# OLM-base-flora.net
KiCad netlist of a schematic drawn in EAGLE
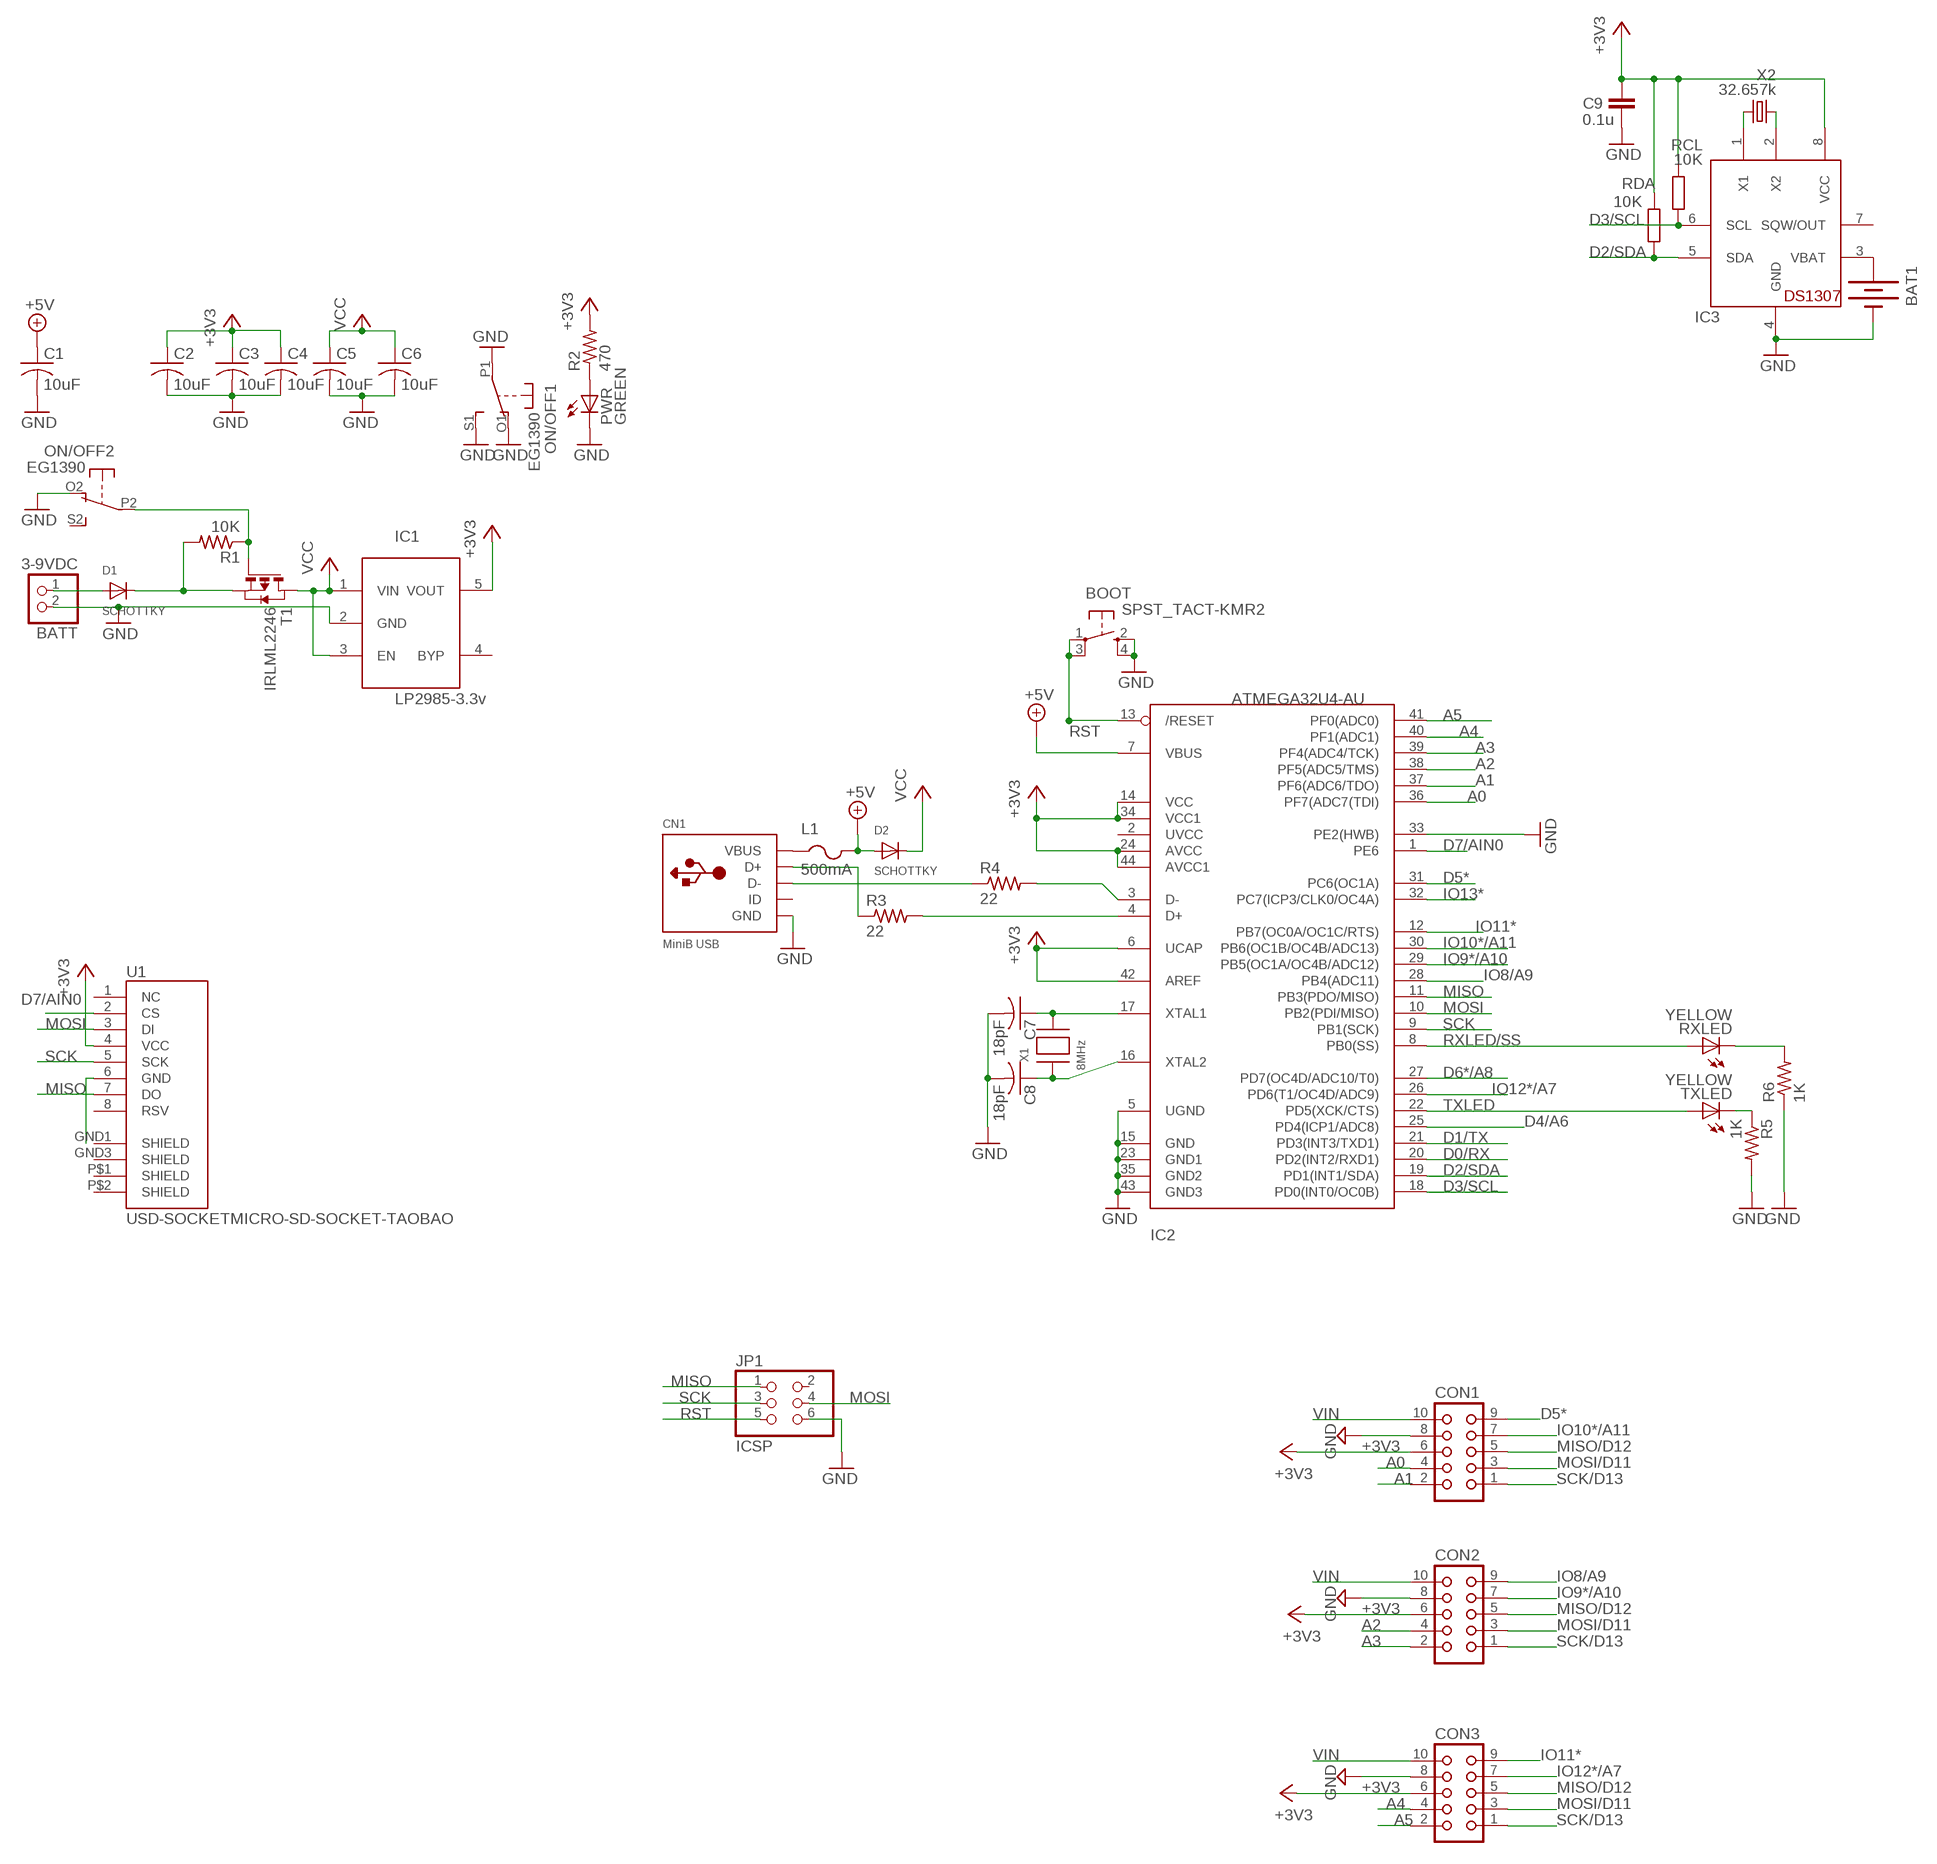
[diagram p0: schematic, sheet 1, part 1 of 2]
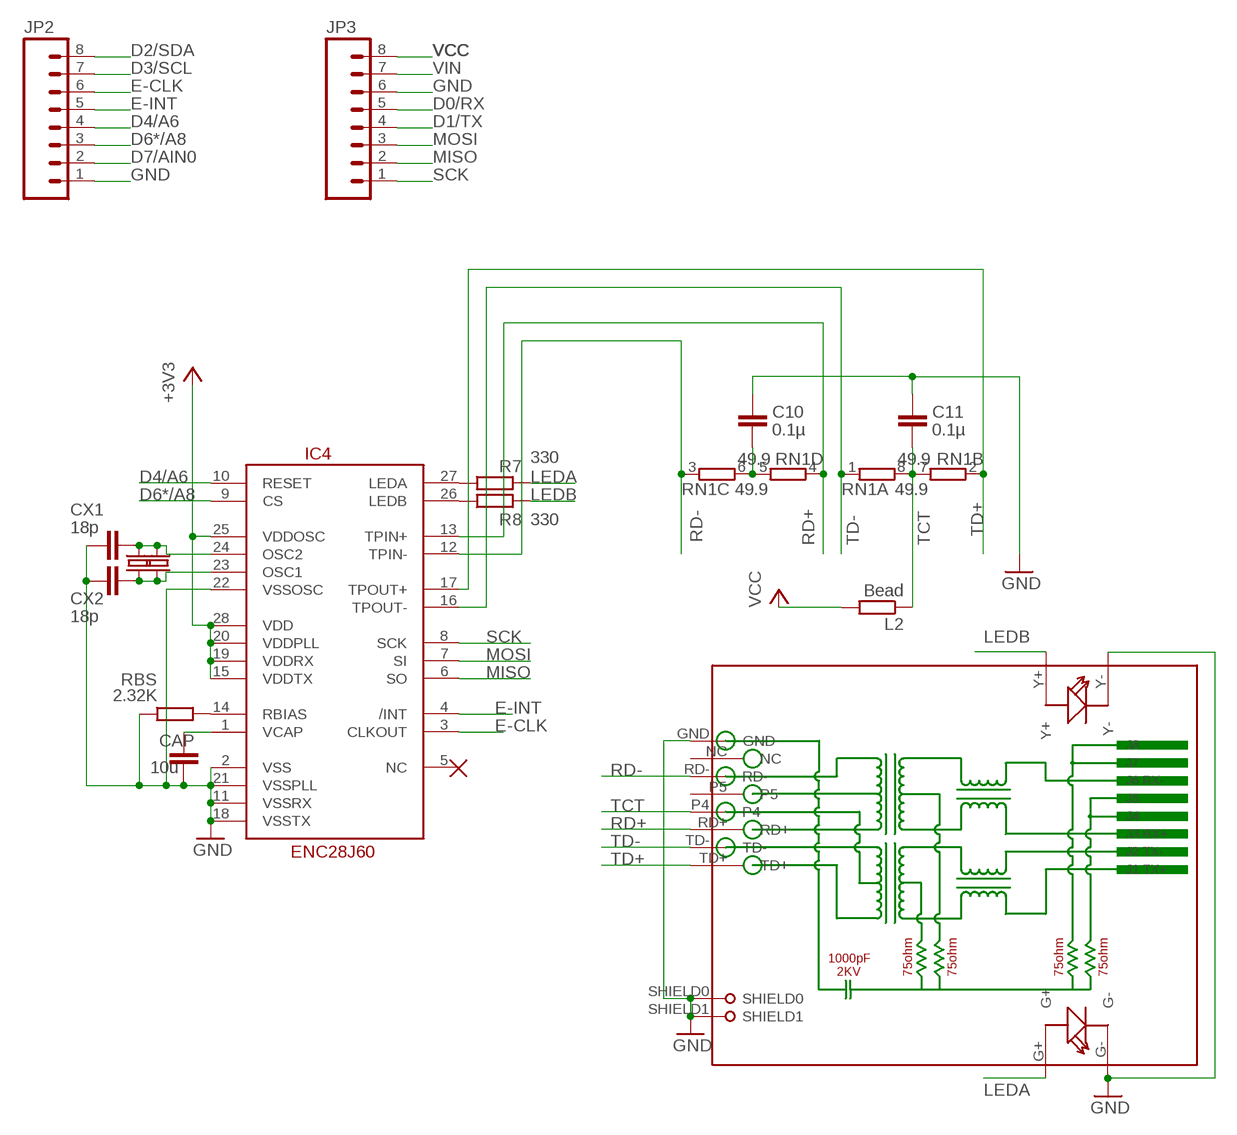
[diagram p1: schematic, sheet 1, part 2 of 2]

(export (version "E")
  (design (tool "Eeschema 10.0.6"))
  (components
    (comp (ref "BAT1")
      (value "BATTERYBATTERY_12MM_SMT")
      (footprint "eagle-import:BATTCON_12MM_SMT")
      (libsource (lib "eagle-import") (part "BATTERYBATTERY_12MM_SMT"))
    )
    (comp (ref "BATT")
      (value "3-9VDC")
      (footprint "eagle-import:JST-PH-2-SMT-RA")
      (libsource (lib "eagle-import") (part "JST_2PIN-SMT-RA"))
    )
    (comp (ref "BOOT")
      (value "SPST_TACT-KMR2")
      (footprint "eagle-import:KMR2")
      (libsource (lib "eagle-import") (part "SPST_TACT-KMR2"))
    )
    (comp (ref "C1")
      (value "10uF")
      (footprint "eagle-import:C0805K")
      (libsource (lib "eagle-import") (part "C-USC0805K"))
    )
    (comp (ref "C2")
      (value "10uF")
      (footprint "eagle-import:C0805K")
      (libsource (lib "eagle-import") (part "C-USC0805K"))
    )
    (comp (ref "C3")
      (value "10uF")
      (footprint "eagle-import:C0805K")
      (libsource (lib "eagle-import") (part "C-USC0805K"))
    )
    (comp (ref "C4")
      (value "10uF")
      (footprint "eagle-import:C0805K")
      (libsource (lib "eagle-import") (part "C-USC0805K"))
    )
    (comp (ref "C5")
      (value "10uF")
      (footprint "eagle-import:C0805K")
      (libsource (lib "eagle-import") (part "C-USC0805K"))
    )
    (comp (ref "C6")
      (value "10uF")
      (footprint "eagle-import:C0805K")
      (libsource (lib "eagle-import") (part "C-USC0805K"))
    )
    (comp (ref "C7")
      (value "18pF")
      (footprint "eagle-import:C0805K")
      (libsource (lib "eagle-import") (part "C-USC0805K"))
    )
    (comp (ref "C8")
      (value "18pF")
      (footprint "eagle-import:C0805K")
      (libsource (lib "eagle-import") (part "C-USC0805K"))
    )
    (comp (ref "C9")
      (value "0.1u")
      (footprint "eagle-import:C0805")
      (libsource (lib "eagle-import") (part "C-EUC0805"))
    )
    (comp (ref "C10")
      (value "0.1µ")
      (footprint "eagle-import:C0805")
      (libsource (lib "eagle-import") (part "resistor_C-EUC0805"))
    )
    (comp (ref "C11")
      (value "0.1µ")
      (footprint "eagle-import:C0805")
      (libsource (lib "eagle-import") (part "resistor_C-EUC0805"))
    )
    (comp (ref "CAP")
      (value "10u")
      (footprint "eagle-import:C0805")
      (libsource (lib "eagle-import") (part "resistor_C-EUC0805"))
    )
    (comp (ref "CN1")
      (value "MiniB USB")
      (footprint "eagle-import:USB-MINIB_LARGER")
      (libsource (lib "eagle-import") (part "USBMINIBLARGE"))
    )
    (comp (ref "CON1")
      (value "CON10L")
      (footprint "eagle-import:CON10L")
      (libsource (lib "eagle-import") (part "CON10L"))
    )
    (comp (ref "CON2")
      (value "CON10L")
      (footprint "eagle-import:CON10L")
      (libsource (lib "eagle-import") (part "CON10L"))
    )
    (comp (ref "CON3")
      (value "CON10L")
      (footprint "eagle-import:CON10L")
      (libsource (lib "eagle-import") (part "CON10L"))
    )
    (comp (ref "CX1")
      (value "18p")
      (footprint "eagle-import:C0805")
      (libsource (lib "eagle-import") (part "resistor_C-EUC0805"))
    )
    (comp (ref "CX2")
      (value "18p")
      (footprint "eagle-import:C0805")
      (libsource (lib "eagle-import") (part "resistor_C-EUC0805"))
    )
    (comp (ref "D1")
      (value "SCHOTTKY")
      (footprint "eagle-import:SOD-123")
      (libsource (lib "eagle-import") (part "DIODESOD-123"))
    )
    (comp (ref "D2")
      (value "SCHOTTKY")
      (footprint "eagle-import:SOD-123")
      (libsource (lib "eagle-import") (part "DIODESOD-123"))
    )
    (comp (ref "IC1")
      (value "LP2985-3.3v")
      (footprint "eagle-import:SOT23-5L")
      (libsource (lib "eagle-import") (part "LP298XS"))
    )
    (comp (ref "IC2")
      (value "ATMEGA32U4-AU")
      (footprint "eagle-import:TQFP44")
      (libsource (lib "eagle-import") (part "ATMEGA32U4-AU"))
    )
    (comp (ref "IC3")
      (value "DS1307")
      (footprint "eagle-import:SO08")
      (libsource (lib "eagle-import") (part "DS1307SOIC"))
    )
    (comp (ref "IC4")
      (value "ENC28J60")
      (footprint "eagle-import:SOIC28WLONG")
      (libsource (lib "eagle-import") (part "ENC28J60SO28LONG"))
    )
    (comp (ref "JP1")
      (value "ICSP")
      (footprint "eagle-import:2X03")
      (libsource (lib "eagle-import") (part "PINHD-2X3"))
    )
    (comp (ref "JP2")
      (value "M08LOCK")
      (footprint "eagle-import:1X08_LOCK")
      (libsource (lib "eagle-import") (part "M08LOCK"))
    )
    (comp (ref "JP3")
      (value "M08LOCK")
      (footprint "eagle-import:1X08_LOCK")
      (libsource (lib "eagle-import") (part "M08LOCK"))
    )
    (comp (ref "L1")
      (value "500mA")
      (footprint "eagle-import:R1206")
      (libsource (lib "eagle-import") (part "PTCFUSE-1206"))
    )
    (comp (ref "L2")
      (value "Bead")
      (footprint "eagle-import:R0805")
      (libsource (lib "eagle-import") (part "R-EU_R0805"))
    )
    (comp (ref "ON/OFF")
      (value "EG1390")
      (footprint "eagle-import:EG1390")
      (libsource (lib "eagle-import") (part "DPDT-EG1390"))
    )
    (comp (ref "PWR")
      (value "GREEN")
      (footprint "eagle-import:CHIPLED_0805")
      (libsource (lib "eagle-import") (part "LEDCHIPLED_0805"))
    )
    (comp (ref "R1")
      (value "10K")
      (footprint "eagle-import:R0805")
      (libsource (lib "eagle-import") (part "R-US_R0805"))
    )
    (comp (ref "R2")
      (value "470")
      (footprint "eagle-import:R0805")
      (libsource (lib "eagle-import") (part "R-US_R0805"))
    )
    (comp (ref "R3")
      (value "22")
      (footprint "eagle-import:R0805")
      (libsource (lib "eagle-import") (part "R-US_R0805"))
    )
    (comp (ref "R4")
      (value "22")
      (footprint "eagle-import:R0805")
      (libsource (lib "eagle-import") (part "R-US_R0805"))
    )
    (comp (ref "R5")
      (value "1K")
      (footprint "eagle-import:R0805")
      (libsource (lib "eagle-import") (part "R-US_R0805"))
    )
    (comp (ref "R6")
      (value "1K")
      (footprint "eagle-import:R0805")
      (libsource (lib "eagle-import") (part "R-US_R0805"))
    )
    (comp (ref "R7")
      (value "330")
      (footprint "eagle-import:R0805")
      (libsource (lib "eagle-import") (part "R-EU_R0805"))
    )
    (comp (ref "R8")
      (value "330")
      (footprint "eagle-import:R0805")
      (libsource (lib "eagle-import") (part "R-EU_R0805"))
    )
    (comp (ref "RBS")
      (value "2.32K")
      (footprint "eagle-import:R0805")
      (libsource (lib "eagle-import") (part "R-EU_R0805"))
    )
    (comp (ref "RCL")
      (value "10K")
      (footprint "eagle-import:R0805")
      (libsource (lib "eagle-import") (part "R-EU_R0805"))
    )
    (comp (ref "RDA")
      (value "10K")
      (footprint "eagle-import:R0805")
      (libsource (lib "eagle-import") (part "R-EU_R0805"))
    )
    (comp (ref "RJ1")
      (value "HR911105A")
      (footprint "eagle-import:HR911105A")
      (libsource (lib "eagle-import") (part "HR911105A"))
    )
    (comp (ref "RN1")
      (value "49.9")
      (footprint "eagle-import:EXB38V")
      (libsource (lib "eagle-import") (part "4R-NEXB38V"))
    )
    (comp (ref "RXLED")
      (value "YELLOW")
      (footprint "eagle-import:CHIPLED_0805")
      (libsource (lib "eagle-import") (part "LEDCHIPLED_0805"))
    )
    (comp (ref "T1")
      (value "IRLML2246")
      (footprint "eagle-import:SOT-23")
      (libsource (lib "eagle-import") (part "PMOSSOT23"))
    )
    (comp (ref "TXLED")
      (value "YELLOW")
      (footprint "eagle-import:CHIPLED_0805")
      (libsource (lib "eagle-import") (part "LEDCHIPLED_0805"))
    )
    (comp (ref "U1")
      (value "USD-SOCKETMICRO-SD-SOCKET-TAOBAO")
      (footprint "eagle-import:MICRO-SD-SOCKET-TAOBAO")
      (libsource (lib "eagle-import") (part "USD-SOCKETMICRO-SD-SOCKET-TAOBAO"))
    )
    (comp (ref "X1")
      (value "8MHz")
      (footprint "eagle-import:NX5032")
      (libsource (lib "eagle-import") (part "XTALNX5032"))
    )
    (comp (ref "X2")
      (value "32.657k")
      (footprint "eagle-import:TC26H")
      (libsource (lib "eagle-import") (part "crystal_CRYSTALTC26H"))
    )
    (comp (ref "X2A")
      (value "25MHz")
      (footprint "eagle-import:CRYSTAL-SMD-10.5X4.8-2PIN")
      (libsource (lib "eagle-import") (part "CRYSTAL10.5X4.8"))
    )
    (comp (ref "X2A1")
      (value "25MHz")
      (footprint "eagle-import:HC49US")
      (libsource (lib "eagle-import") (part "CRYSTALHC49US"))
    )
  )
  (nets
    (net (code "1") (name "+3V3") (class "Default")
      (node (ref "C2") (pin "1") (pinfunction "1_1") (pintype "passive"))
      (node (ref "C3") (pin "1") (pinfunction "1_1") (pintype "passive"))
      (node (ref "C4") (pin "1") (pinfunction "1_1") (pintype "passive"))
      (node (ref "C9") (pin "1") (pinfunction "1_1") (pintype "passive"))
      (node (ref "CON1") (pin "6") (pinfunction "6_6") (pintype "passive"))
      (node (ref "CON2") (pin "6") (pinfunction "6_6") (pintype "passive"))
      (node (ref "CON3") (pin "6") (pinfunction "6_6") (pintype "passive"))
      (node (ref "IC1") (pin "5") (pinfunction "VOUT_5") (pintype "bidirectional"))
      (node (ref "IC2") (pin "14") (pinfunction "VCC_14") (pintype "bidirectional"))
      (node (ref "IC2") (pin "24") (pinfunction "AVCC_24") (pintype "bidirectional"))
      (node (ref "IC2") (pin "34") (pinfunction "VCC1_34") (pintype "bidirectional"))
      (node (ref "IC2") (pin "42") (pinfunction "AREF_42") (pintype "bidirectional"))
      (node (ref "IC2") (pin "44") (pinfunction "AVCC1_44") (pintype "bidirectional"))
      (node (ref "IC2") (pin "6") (pinfunction "UCAP_6") (pintype "bidirectional"))
      (node (ref "IC3") (pin "8") (pinfunction "VCC_8") (pintype "power_in"))
      (node (ref "IC4") (pin "15") (pinfunction "VDDTX_15") (pintype "bidirectional"))
      (node (ref "IC4") (pin "19") (pinfunction "VDDRX_19") (pintype "bidirectional"))
      (node (ref "IC4") (pin "20") (pinfunction "VDDPLL_20") (pintype "bidirectional"))
      (node (ref "IC4") (pin "25") (pinfunction "VDDOSC_25") (pintype "bidirectional"))
      (node (ref "IC4") (pin "28") (pinfunction "VDD_28") (pintype "bidirectional"))
      (node (ref "R2") (pin "2") (pinfunction "2_2") (pintype "passive"))
      (node (ref "RCL") (pin "1") (pinfunction "1_1") (pintype "passive"))
      (node (ref "RDA") (pin "1") (pinfunction "1_1") (pintype "passive"))
      (node (ref "U1") (pin "4") (pinfunction "VCC_4") (pintype "bidirectional"))
    )
    (net (code "2") (name "+5V") (class "Default")
      (node (ref "C1") (pin "1") (pinfunction "1_1") (pintype "passive"))
      (node (ref "D2") (pin "A") (pinfunction "A_A") (pintype "passive"))
      (node (ref "IC2") (pin "7") (pinfunction "VBUS_7") (pintype "bidirectional"))
      (node (ref "L1") (pin "2") (pinfunction "2_2") (pintype "passive"))
    )
    (net (code "3") (name "/A0") (class "Default")
      (node (ref "CON1") (pin "4") (pinfunction "4_4") (pintype "passive"))
      (node (ref "IC2") (pin "36") (pinfunction "PF7(ADC7(TDI)_36") (pintype "bidirectional"))
    )
    (net (code "4") (name "/A1") (class "Default")
      (node (ref "CON1") (pin "2") (pinfunction "2_2") (pintype "passive"))
      (node (ref "IC2") (pin "37") (pinfunction "PF6(ADC6/TDO)_37") (pintype "bidirectional"))
    )
    (net (code "5") (name "/A2") (class "Default")
      (node (ref "CON2") (pin "4") (pinfunction "4_4") (pintype "passive"))
      (node (ref "IC2") (pin "38") (pinfunction "PF5(ADC5/TMS)_38") (pintype "bidirectional"))
    )
    (net (code "6") (name "/A3") (class "Default")
      (node (ref "CON2") (pin "2") (pinfunction "2_2") (pintype "passive"))
      (node (ref "IC2") (pin "39") (pinfunction "PF4(ADC4/TCK)_39") (pintype "bidirectional"))
    )
    (net (code "7") (name "/A4") (class "Default")
      (node (ref "CON3") (pin "4") (pinfunction "4_4") (pintype "passive"))
      (node (ref "IC2") (pin "40") (pinfunction "PF1(ADC1)_40") (pintype "bidirectional"))
    )
    (net (code "8") (name "/A5") (class "Default")
      (node (ref "CON3") (pin "2") (pinfunction "2_2") (pintype "passive"))
      (node (ref "IC2") (pin "41") (pinfunction "PF0(ADC0)_41") (pintype "bidirectional"))
    )
    (net (code "9") (name "/D0{slash}RX") (class "Default")
      (node (ref "IC2") (pin "20") (pinfunction "PD2(INT2/RXD1)_20") (pintype "bidirectional"))
      (node (ref "JP3") (pin "5") (pinfunction "5_5") (pintype "passive"))
    )
    (net (code "10") (name "/D1{slash}TX") (class "Default")
      (node (ref "IC2") (pin "21") (pinfunction "PD3(INT3/TXD1)_21") (pintype "bidirectional"))
      (node (ref "JP3") (pin "4") (pinfunction "4_4") (pintype "passive"))
    )
    (net (code "11") (name "/D2{slash}SDA") (class "Default")
      (node (ref "IC2") (pin "19") (pinfunction "PD1(INT1/SDA)_19") (pintype "bidirectional"))
      (node (ref "IC3") (pin "5") (pinfunction "SDA_5") (pintype "bidirectional"))
      (node (ref "JP2") (pin "8") (pinfunction "8_8") (pintype "passive"))
      (node (ref "RDA") (pin "2") (pinfunction "2_2") (pintype "passive"))
    )
    (net (code "12") (name "/D3{slash}SCL") (class "Default")
      (node (ref "IC2") (pin "18") (pinfunction "PD0(INT0/OC0B)_18") (pintype "bidirectional"))
      (node (ref "IC3") (pin "6") (pinfunction "SCL_6") (pintype "bidirectional"))
      (node (ref "JP2") (pin "7") (pinfunction "7_7") (pintype "passive"))
      (node (ref "RCL") (pin "2") (pinfunction "2_2") (pintype "passive"))
    )
    (net (code "13") (name "/D4{slash}A6") (class "Default")
      (node (ref "IC2") (pin "25") (pinfunction "PD4(ICP1/ADC8)_25") (pintype "bidirectional"))
      (node (ref "IC4") (pin "10") (pinfunction "RESET_10") (pintype "bidirectional"))
      (node (ref "JP2") (pin "4") (pinfunction "4_4") (pintype "passive"))
    )
    (net (code "14") (name "/D5*") (class "Default")
      (node (ref "CON1") (pin "9") (pinfunction "9_9") (pintype "passive"))
      (node (ref "IC2") (pin "31") (pinfunction "PC6(OC1A)_31") (pintype "bidirectional"))
    )
    (net (code "15") (name "/D6*{slash}A8") (class "Default")
      (node (ref "IC2") (pin "27") (pinfunction "PD7(OC4D/ADC10/T0)_27") (pintype "bidirectional"))
      (node (ref "IC4") (pin "9") (pinfunction "CS_9") (pintype "bidirectional"))
      (node (ref "JP2") (pin "3") (pinfunction "3_3") (pintype "passive"))
    )
    (net (code "16") (name "/D7{slash}AIN0") (class "Default")
      (node (ref "IC2") (pin "1") (pinfunction "PE6_1") (pintype "bidirectional"))
      (node (ref "JP2") (pin "2") (pinfunction "2_2") (pintype "passive"))
      (node (ref "U1") (pin "2") (pinfunction "CS_2") (pintype "bidirectional"))
    )
    (net (code "17") (name "/E-CLK") (class "Default")
      (node (ref "IC4") (pin "3") (pinfunction "CLKOUT_3") (pintype "bidirectional"))
      (node (ref "JP2") (pin "6") (pinfunction "6_6") (pintype "passive"))
    )
    (net (code "18") (name "/E-INT") (class "Default")
      (node (ref "IC4") (pin "4") (pinfunction "/INT_4") (pintype "bidirectional"))
      (node (ref "JP2") (pin "5") (pinfunction "5_5") (pintype "passive"))
    )
    (net (code "19") (name "/IO8{slash}A9") (class "Default")
      (node (ref "CON2") (pin "9") (pinfunction "9_9") (pintype "passive"))
      (node (ref "IC2") (pin "28") (pinfunction "PB4(ADC11)_28") (pintype "bidirectional"))
    )
    (net (code "20") (name "/IO9*{slash}A10") (class "Default")
      (node (ref "CON2") (pin "7") (pinfunction "7_7") (pintype "passive"))
      (node (ref "IC2") (pin "29") (pinfunction "PB5(OC1A/OC4B/ADC12)_29") (pintype "bidirectional"))
    )
    (net (code "21") (name "/IO10*{slash}A11") (class "Default")
      (node (ref "CON1") (pin "7") (pinfunction "7_7") (pintype "passive"))
      (node (ref "IC2") (pin "30") (pinfunction "PB6(OC1B/OC4B/ADC13)_30") (pintype "bidirectional"))
    )
    (net (code "22") (name "/IO11*") (class "Default")
      (node (ref "CON3") (pin "9") (pinfunction "9_9") (pintype "passive"))
      (node (ref "IC2") (pin "12") (pinfunction "PB7(OC0A/OC1C/RTS)_12") (pintype "bidirectional"))
    )
    (net (code "23") (name "/IO12*{slash}A7") (class "Default")
      (node (ref "CON3") (pin "7") (pinfunction "7_7") (pintype "passive"))
      (node (ref "IC2") (pin "26") (pinfunction "PD6(T1/OC4D/ADC9)_26") (pintype "bidirectional"))
    )
    (net (code "24") (name "/IO13*") (class "Default")
      (node (ref "IC2") (pin "32") (pinfunction "PC7(ICP3/CLK0/OC4A)_32") (pintype "bidirectional"))
    )
    (net (code "25") (name "/LEDA") (class "Default")
      (node (ref "R7") (pin "2") (pinfunction "2_2") (pintype "passive"))
      (node (ref "RJ1") (pin "G+") (pinfunction "G+_G+") (pintype "bidirectional"))
    )
    (net (code "26") (name "/LEDB") (class "Default")
      (node (ref "R8") (pin "2") (pinfunction "2_2") (pintype "passive"))
      (node (ref "RJ1") (pin "Y+") (pinfunction "Y+_Y+") (pintype "bidirectional"))
    )
    (net (code "27") (name "/MISO") (class "Default")
      (node (ref "IC2") (pin "11") (pinfunction "PB3(PDO/MISO)_11") (pintype "bidirectional"))
      (node (ref "IC4") (pin "6") (pinfunction "SO_6") (pintype "bidirectional"))
      (node (ref "JP1") (pin "1") (pinfunction "1_1") (pintype "passive"))
      (node (ref "JP3") (pin "2") (pinfunction "2_2") (pintype "passive"))
      (node (ref "U1") (pin "7") (pinfunction "DO_7") (pintype "bidirectional"))
    )
    (net (code "28") (name "/MISO{slash}D12") (class "Default")
      (node (ref "CON1") (pin "5") (pinfunction "5_5") (pintype "passive"))
      (node (ref "CON2") (pin "5") (pinfunction "5_5") (pintype "passive"))
      (node (ref "CON3") (pin "5") (pinfunction "5_5") (pintype "passive"))
    )
    (net (code "29") (name "/MOSI") (class "Default")
      (node (ref "IC2") (pin "10") (pinfunction "PB2(PDI/MISO)_10") (pintype "bidirectional"))
      (node (ref "IC4") (pin "7") (pinfunction "SI_7") (pintype "bidirectional"))
      (node (ref "JP1") (pin "4") (pinfunction "4_4") (pintype "passive"))
      (node (ref "JP3") (pin "3") (pinfunction "3_3") (pintype "passive"))
      (node (ref "U1") (pin "3") (pinfunction "DI_3") (pintype "bidirectional"))
    )
    (net (code "30") (name "/MOSI{slash}D11") (class "Default")
      (node (ref "CON1") (pin "3") (pinfunction "3_3") (pintype "passive"))
      (node (ref "CON2") (pin "3") (pinfunction "3_3") (pintype "passive"))
      (node (ref "CON3") (pin "3") (pinfunction "3_3") (pintype "passive"))
    )
    (net (code "31") (name "/RD+") (class "Default")
      (node (ref "IC4") (pin "13") (pinfunction "TPIN+_13") (pintype "bidirectional"))
      (node (ref "RJ1") (pin "RD+") (pinfunction "RD+_RD+") (pintype "bidirectional"))
      (node (ref "RN1") (pin "4") (pinfunction "1_4") (pintype "passive"))
    )
    (net (code "32") (name "/RD-") (class "Default")
      (node (ref "IC4") (pin "12") (pinfunction "TPIN-_12") (pintype "bidirectional"))
      (node (ref "RJ1") (pin "RD-") (pinfunction "RD-_RD-") (pintype "bidirectional"))
      (node (ref "RN1") (pin "3") (pinfunction "1_3") (pintype "passive"))
    )
    (net (code "33") (name "/RST") (class "Default")
      (node (ref "BOOT") (pin "1") (pinfunction "P_1") (pintype "passive"))
      (node (ref "BOOT") (pin "3") (pinfunction "P1_3") (pintype "passive"))
      (node (ref "IC2") (pin "13") (pinfunction "/RESET_13") (pintype "bidirectional"))
      (node (ref "JP1") (pin "5") (pinfunction "5_5") (pintype "passive"))
    )
    (net (code "34") (name "/RXLED{slash}SS") (class "Default")
      (node (ref "IC2") (pin "8") (pinfunction "PB0(SS)_8") (pintype "bidirectional"))
      (node (ref "RXLED") (pin "A") (pinfunction "A_A") (pintype "passive"))
    )
    (net (code "35") (name "/SCK") (class "Default")
      (node (ref "IC2") (pin "9") (pinfunction "PB1(SCK)_9") (pintype "bidirectional"))
      (node (ref "IC4") (pin "8") (pinfunction "SCK_8") (pintype "bidirectional"))
      (node (ref "JP1") (pin "3") (pinfunction "3_3") (pintype "passive"))
      (node (ref "JP3") (pin "1") (pinfunction "1_1") (pintype "passive"))
      (node (ref "U1") (pin "5") (pinfunction "SCK_5") (pintype "bidirectional"))
    )
    (net (code "36") (name "/SCK{slash}D13") (class "Default")
      (node (ref "CON1") (pin "1") (pinfunction "1_1") (pintype "passive"))
      (node (ref "CON2") (pin "1") (pinfunction "1_1") (pintype "passive"))
      (node (ref "CON3") (pin "1") (pinfunction "1_1") (pintype "passive"))
    )
    (net (code "37") (name "/TCT") (class "Default")
      (node (ref "C11") (pin "2") (pinfunction "2_2") (pintype "passive"))
      (node (ref "L2") (pin "1") (pinfunction "1_1") (pintype "passive"))
      (node (ref "RJ1") (pin "P4") (pinfunction "P4_P4") (pintype "bidirectional"))
      (node (ref "RN1") (pin "7") (pinfunction "2_7") (pintype "passive"))
      (node (ref "RN1") (pin "8") (pinfunction "2_8") (pintype "passive"))
    )
    (net (code "38") (name "/TD+") (class "Default")
      (node (ref "IC4") (pin "17") (pinfunction "TPOUT+_17") (pintype "bidirectional"))
      (node (ref "RJ1") (pin "TD+") (pinfunction "TD+_TD+") (pintype "bidirectional"))
      (node (ref "RN1") (pin "2") (pinfunction "1_2") (pintype "passive"))
    )
    (net (code "39") (name "/TD-") (class "Default")
      (node (ref "IC4") (pin "16") (pinfunction "TPOUT-_16") (pintype "bidirectional"))
      (node (ref "RJ1") (pin "TD-") (pinfunction "TD-_TD-") (pintype "bidirectional"))
      (node (ref "RN1") (pin "1") (pinfunction "1_1") (pintype "passive"))
    )
    (net (code "40") (name "/TXLED") (class "Default")
      (node (ref "IC2") (pin "22") (pinfunction "PD5(XCK/CTS)_22") (pintype "bidirectional"))
      (node (ref "TXLED") (pin "A") (pinfunction "A_A") (pintype "passive"))
    )
    (net (code "41") (name "/VIN") (class "Default")
      (node (ref "CON1") (pin "10") (pinfunction "10_10") (pintype "passive"))
      (node (ref "CON2") (pin "10") (pinfunction "10_10") (pintype "passive"))
      (node (ref "CON3") (pin "10") (pinfunction "10_10") (pintype "passive"))
      (node (ref "JP3") (pin "7") (pinfunction "7_7") (pintype "passive"))
    )
    (net (code "42") (name "GND") (class "Default")
      (node (ref "BAT1") (pin "P$1") (pinfunction "-_P$1") (pintype "power_in"))
      (node (ref "BATT") (pin "2") (pinfunction "1_2") (pintype "passive"))
      (node (ref "BOOT") (pin "2") (pinfunction "S_2") (pintype "passive"))
      (node (ref "BOOT") (pin "4") (pinfunction "S1_4") (pintype "passive"))
      (node (ref "C1") (pin "2") (pinfunction "2_2") (pintype "passive"))
      (node (ref "C10") (pin "1") (pinfunction "1_1") (pintype "passive"))
      (node (ref "C11") (pin "1") (pinfunction "1_1") (pintype "passive"))
      (node (ref "C2") (pin "2") (pinfunction "2_2") (pintype "passive"))
      (node (ref "C3") (pin "2") (pinfunction "2_2") (pintype "passive"))
      (node (ref "C4") (pin "2") (pinfunction "2_2") (pintype "passive"))
      (node (ref "C5") (pin "2") (pinfunction "2_2") (pintype "passive"))
      (node (ref "C6") (pin "2") (pinfunction "2_2") (pintype "passive"))
      (node (ref "C7") (pin "2") (pinfunction "2_2") (pintype "passive"))
      (node (ref "C8") (pin "2") (pinfunction "2_2") (pintype "passive"))
      (node (ref "C9") (pin "2") (pinfunction "2_2") (pintype "passive"))
      (node (ref "CAP") (pin "2") (pinfunction "2_2") (pintype "passive"))
      (node (ref "CN1") (pin "GND") (pinfunction "GND_GND") (pintype "power_in"))
      (node (ref "CON1") (pin "8") (pinfunction "8_8") (pintype "passive"))
      (node (ref "CON2") (pin "8") (pinfunction "8_8") (pintype "passive"))
      (node (ref "CON3") (pin "8") (pinfunction "8_8") (pintype "passive"))
      (node (ref "CX1") (pin "2") (pinfunction "2_2") (pintype "passive"))
      (node (ref "CX2") (pin "2") (pinfunction "2_2") (pintype "passive"))
      (node (ref "IC1") (pin "2") (pinfunction "GND_2") (pintype "bidirectional"))
      (node (ref "IC2") (pin "15") (pinfunction "GND_15") (pintype "bidirectional"))
      (node (ref "IC2") (pin "23") (pinfunction "GND1_23") (pintype "bidirectional"))
      (node (ref "IC2") (pin "33") (pinfunction "PE2(HWB)_33") (pintype "bidirectional"))
      (node (ref "IC2") (pin "35") (pinfunction "GND2_35") (pintype "bidirectional"))
      (node (ref "IC2") (pin "43") (pinfunction "GND3_43") (pintype "bidirectional"))
      (node (ref "IC2") (pin "5") (pinfunction "UGND_5") (pintype "bidirectional"))
      (node (ref "IC3") (pin "4") (pinfunction "GND_4") (pintype "power_in"))
      (node (ref "IC4") (pin "11") (pinfunction "VSSRX_11") (pintype "bidirectional"))
      (node (ref "IC4") (pin "18") (pinfunction "VSSTX_18") (pintype "bidirectional"))
      (node (ref "IC4") (pin "2") (pinfunction "VSS_2") (pintype "bidirectional"))
      (node (ref "IC4") (pin "21") (pinfunction "VSSPLL_21") (pintype "bidirectional"))
      (node (ref "IC4") (pin "22") (pinfunction "VSSOSC_22") (pintype "bidirectional"))
      (node (ref "JP1") (pin "6") (pinfunction "6_6") (pintype "passive"))
      (node (ref "JP2") (pin "1") (pinfunction "1_1") (pintype "passive"))
      (node (ref "JP3") (pin "6") (pinfunction "6_6") (pintype "passive"))
      (node (ref "ON/OFF") (pin "O1") (pinfunction "O_O1") (pintype "passive"))
      (node (ref "ON/OFF") (pin "O2") (pinfunction "O_O2") (pintype "passive"))
      (node (ref "ON/OFF") (pin "P1") (pinfunction "P_P1") (pintype "passive"))
      (node (ref "ON/OFF") (pin "S1") (pinfunction "S_S1") (pintype "passive"))
      (node (ref "PWR") (pin "C") (pinfunction "C_C") (pintype "passive"))
      (node (ref "R5") (pin "2") (pinfunction "2_2") (pintype "passive"))
      (node (ref "R6") (pin "1") (pinfunction "1_1") (pintype "passive"))
      (node (ref "RBS") (pin "1") (pinfunction "1_1") (pintype "passive"))
      (node (ref "RJ1") (pin "G-") (pinfunction "G-_G-") (pintype "bidirectional"))
      (node (ref "RJ1") (pin "GND") (pinfunction "GND_GND") (pintype "bidirectional"))
      (node (ref "RJ1") (pin "SHIELD0") (pinfunction "SHIELD0_SHIELD0") (pintype "bidirectional"))
      (node (ref "RJ1") (pin "SHIELD1") (pinfunction "SHIELD1_SHIELD1") (pintype "bidirectional"))
      (node (ref "RJ1") (pin "Y-") (pinfunction "Y-_Y-") (pintype "bidirectional"))
      (node (ref "U1") (pin "6") (pinfunction "GND_6") (pintype "bidirectional"))
    )
    (net (code "43") (name "Net-(BAT1-+)") (class "Default")
      (node (ref "BAT1") (pin "P$2") (pinfunction "+_P$2") (pintype "power_in"))
      (node (ref "IC3") (pin "3") (pinfunction "VBAT_3") (pintype "power_in"))
    )
    (net (code "44") (name "Net-(BATT-2)") (class "Default")
      (node (ref "BATT") (pin "1") (pinfunction "2_1") (pintype "passive"))
      (node (ref "D1") (pin "A") (pinfunction "A_A") (pintype "passive"))
    )
    (net (code "45") (name "Net-(CN1-PadD+)") (class "Default")
      (node (ref "CN1") (pin "D+") (pinfunction "D+_D+") (pintype "bidirectional"))
      (node (ref "R3") (pin "1") (pinfunction "1_1") (pintype "passive"))
    )
    (net (code "46") (name "Net-(CN1-PadD-)") (class "Default")
      (node (ref "CN1") (pin "D-") (pinfunction "D-_D-") (pintype "bidirectional"))
      (node (ref "R4") (pin "1") (pinfunction "1_1") (pintype "passive"))
    )
    (net (code "47") (name "Net-(CN1-PadVBUS)") (class "Default")
      (node (ref "CN1") (pin "VBUS") (pinfunction "VBUS_VBUS") (pintype "power_in"))
      (node (ref "L1") (pin "1") (pinfunction "1_1") (pintype "passive"))
    )
    (net (code "48") (name "Net-(IC2-D+)") (class "Default")
      (node (ref "IC2") (pin "4") (pinfunction "D+_4") (pintype "bidirectional"))
      (node (ref "R3") (pin "2") (pinfunction "2_2") (pintype "passive"))
    )
    (net (code "49") (name "Net-(IC2-D-)") (class "Default")
      (node (ref "IC2") (pin "3") (pinfunction "D-_3") (pintype "bidirectional"))
      (node (ref "R4") (pin "2") (pinfunction "2_2") (pintype "passive"))
    )
    (net (code "50") (name "Net-(IC2-XTAL1)") (class "Default")
      (node (ref "C7") (pin "1") (pinfunction "1_1") (pintype "passive"))
      (node (ref "IC2") (pin "17") (pinfunction "XTAL1_17") (pintype "bidirectional"))
      (node (ref "X1") (pin "P$2") (pinfunction "P$2_P$2") (pintype "bidirectional"))
    )
    (net (code "51") (name "Net-(IC2-XTAL2)") (class "Default")
      (node (ref "C8") (pin "1") (pinfunction "1_1") (pintype "passive"))
      (node (ref "IC2") (pin "16") (pinfunction "XTAL2_16") (pintype "bidirectional"))
      (node (ref "X1") (pin "P$1") (pinfunction "P$1_P$1") (pintype "bidirectional"))
    )
    (net (code "52") (name "Net-(IC3-X1)") (class "Default")
      (node (ref "IC3") (pin "1") (pinfunction "X1_1") (pintype "passive"))
      (node (ref "X2") (pin "1") (pinfunction "1_1") (pintype "passive"))
    )
    (net (code "53") (name "Net-(IC3-X2)") (class "Default")
      (node (ref "IC3") (pin "2") (pinfunction "X2_2") (pintype "passive"))
      (node (ref "X2") (pin "2") (pinfunction "2_2") (pintype "passive"))
    )
    (net (code "54") (name "Net-(IC4-LEDA)") (class "Default")
      (node (ref "IC4") (pin "27") (pinfunction "LEDA_27") (pintype "bidirectional"))
      (node (ref "R7") (pin "1") (pinfunction "1_1") (pintype "passive"))
    )
    (net (code "55") (name "Net-(IC4-LEDB)") (class "Default")
      (node (ref "IC4") (pin "26") (pinfunction "LEDB_26") (pintype "bidirectional"))
      (node (ref "R8") (pin "1") (pinfunction "1_1") (pintype "passive"))
    )
    (net (code "56") (name "Net-(IC4-OSC1)") (class "Default")
      (node (ref "CX2") (pin "1") (pinfunction "1_1") (pintype "passive"))
      (node (ref "IC4") (pin "23") (pinfunction "OSC1_23") (pintype "bidirectional"))
      (node (ref "X2A") (pin "P$1") (pinfunction "1_P$1") (pintype "passive"))
      (node (ref "X2A1") (pin "1") (pinfunction "1_1") (pintype "passive"))
    )
    (net (code "57") (name "Net-(IC4-OSC2)") (class "Default")
      (node (ref "CX1") (pin "1") (pinfunction "1_1") (pintype "passive"))
      (node (ref "IC4") (pin "24") (pinfunction "OSC2_24") (pintype "bidirectional"))
      (node (ref "X2A") (pin "P$2") (pinfunction "2_P$2") (pintype "passive"))
      (node (ref "X2A1") (pin "2") (pinfunction "2_2") (pintype "passive"))
    )
    (net (code "58") (name "Net-(IC4-RBIAS)") (class "Default")
      (node (ref "IC4") (pin "14") (pinfunction "RBIAS_14") (pintype "bidirectional"))
      (node (ref "RBS") (pin "2") (pinfunction "2_2") (pintype "passive"))
    )
    (net (code "59") (name "Net-(IC4-VCAP)") (class "Default")
      (node (ref "CAP") (pin "1") (pinfunction "1_1") (pintype "passive"))
      (node (ref "IC4") (pin "1") (pinfunction "VCAP_1") (pintype "bidirectional"))
    )
    (net (code "60") (name "Net-(ON/OFFB-P)") (class "Default")
      (node (ref "ON/OFF") (pin "P2") (pinfunction "P_P2") (pintype "passive"))
      (node (ref "R1") (pin "1") (pinfunction "1_1") (pintype "passive"))
      (node (ref "T1") (pin "3") (pinfunction "G_3") (pintype "passive"))
    )
    (net (code "61") (name "Net-(PWR-PadA)") (class "Default")
      (node (ref "PWR") (pin "A") (pinfunction "A_A") (pintype "passive"))
      (node (ref "R2") (pin "1") (pinfunction "1_1") (pintype "passive"))
    )
    (net (code "62") (name "Net-(R5-Pad1)") (class "Default")
      (node (ref "R5") (pin "1") (pinfunction "1_1") (pintype "passive"))
      (node (ref "TXLED") (pin "C") (pinfunction "C_C") (pintype "passive"))
    )
    (net (code "63") (name "Net-(R6-Pad2)") (class "Default")
      (node (ref "R6") (pin "2") (pinfunction "2_2") (pintype "passive"))
      (node (ref "RXLED") (pin "C") (pinfunction "C_C") (pintype "passive"))
    )
    (net (code "64") (name "Net-(RN1C-2)") (class "Default")
      (node (ref "C10") (pin "2") (pinfunction "2_2") (pintype "passive"))
      (node (ref "RN1") (pin "5") (pinfunction "2_5") (pintype "passive"))
      (node (ref "RN1") (pin "6") (pinfunction "2_6") (pintype "passive"))
    )
    (net (code "65") (name "Net-(T1-S)") (class "Default")
      (node (ref "D1") (pin "C") (pinfunction "C_C") (pintype "passive"))
      (node (ref "R1") (pin "2") (pinfunction "2_2") (pintype "passive"))
      (node (ref "T1") (pin "2") (pinfunction "S_2") (pintype "passive"))
    )
    (net (code "66") (name "VCC") (class "Default")
      (node (ref "C5") (pin "1") (pinfunction "1_1") (pintype "passive"))
      (node (ref "C6") (pin "1") (pinfunction "1_1") (pintype "passive"))
      (node (ref "D2") (pin "C") (pinfunction "C_C") (pintype "passive"))
      (node (ref "IC1") (pin "1") (pinfunction "VIN_1") (pintype "bidirectional"))
      (node (ref "IC1") (pin "3") (pinfunction "EN_3") (pintype "bidirectional"))
      (node (ref "JP3") (pin "8") (pinfunction "8_8") (pintype "passive"))
      (node (ref "L2") (pin "2") (pinfunction "2_2") (pintype "passive"))
      (node (ref "T1") (pin "1") (pinfunction "D_1") (pintype "passive"))
    )
    (net (code "67") (name "unconnected-(CN1-PadID)") (class "Default")
      (node (ref "CN1") (pin "ID") (pinfunction "ID_ID") (pintype "bidirectional"))
    )
    (net (code "68") (name "unconnected-(IC1-BYP-Pad4)") (class "Default")
      (node (ref "IC1") (pin "4") (pinfunction "BYP_4") (pintype "bidirectional"))
    )
    (net (code "69") (name "unconnected-(IC2-UVCC-Pad2)") (class "Default")
      (node (ref "IC2") (pin "2") (pinfunction "UVCC_2") (pintype "bidirectional"))
    )
    (net (code "70") (name "unconnected-(IC3-SQW{slash}OUT-Pad7)") (class "Default")
      (node (ref "IC3") (pin "7") (pinfunction "SQW/OUT_7") (pintype "bidirectional"))
    )
    (net (code "71") (name "unconnected-(IC4-NC-Pad5)") (class "Default")
      (node (ref "IC4") (pin "5") (pinfunction "NC_5") (pintype "bidirectional"))
    )
    (net (code "72") (name "unconnected-(JP1-Pad2)") (class "Default")
      (node (ref "JP1") (pin "2") (pinfunction "2_2") (pintype "passive"))
    )
    (net (code "73") (name "unconnected-(ON/OFFB-S-PadS2)") (class "Default")
      (node (ref "ON/OFF") (pin "S2") (pinfunction "S_S2") (pintype "passive"))
    )
    (net (code "74") (name "unconnected-(RJ1-PadNC)") (class "Default")
      (node (ref "RJ1") (pin "NC") (pinfunction "NC_NC") (pintype "bidirectional"))
    )
    (net (code "75") (name "unconnected-(RJ1-PadP5)") (class "Default")
      (node (ref "RJ1") (pin "P5") (pinfunction "P5_P5") (pintype "bidirectional"))
    )
    (net (code "76") (name "unconnected-(U1-NC-Pad1)") (class "Default")
      (node (ref "U1") (pin "1") (pinfunction "NC_1") (pintype "bidirectional"))
    )
    (net (code "77") (name "unconnected-(U1-RSV-Pad8)") (class "Default")
      (node (ref "U1") (pin "8") (pinfunction "RSV_8") (pintype "bidirectional"))
    )
    (net (code "78") (name "unconnected-(U1-SHIELD-PadGND1)") (class "Default")
      (node (ref "U1") (pin "GND1") (pinfunction "SHIELD_GND1") (pintype "bidirectional"))
    )
    (net (code "79") (name "unconnected-(U1-SHIELD-PadGND3)") (class "Default")
      (node (ref "U1") (pin "GND3") (pinfunction "SHIELD_GND3") (pintype "bidirectional"))
    )
    (net (code "80") (name "unconnected-(U1-SHIELD-PadP$1)") (class "Default")
      (node (ref "U1") (pin "P$1") (pinfunction "SHIELD_P$1") (pintype "bidirectional"))
    )
    (net (code "81") (name "unconnected-(U1-SHIELD-PadP$2)") (class "Default")
      (node (ref "U1") (pin "P$2") (pinfunction "SHIELD_P$2") (pintype "bidirectional"))
    )
  )
)
